# Secondary_Board_1_1.net
KiCad netlist of a schematic drawn in EAGLE
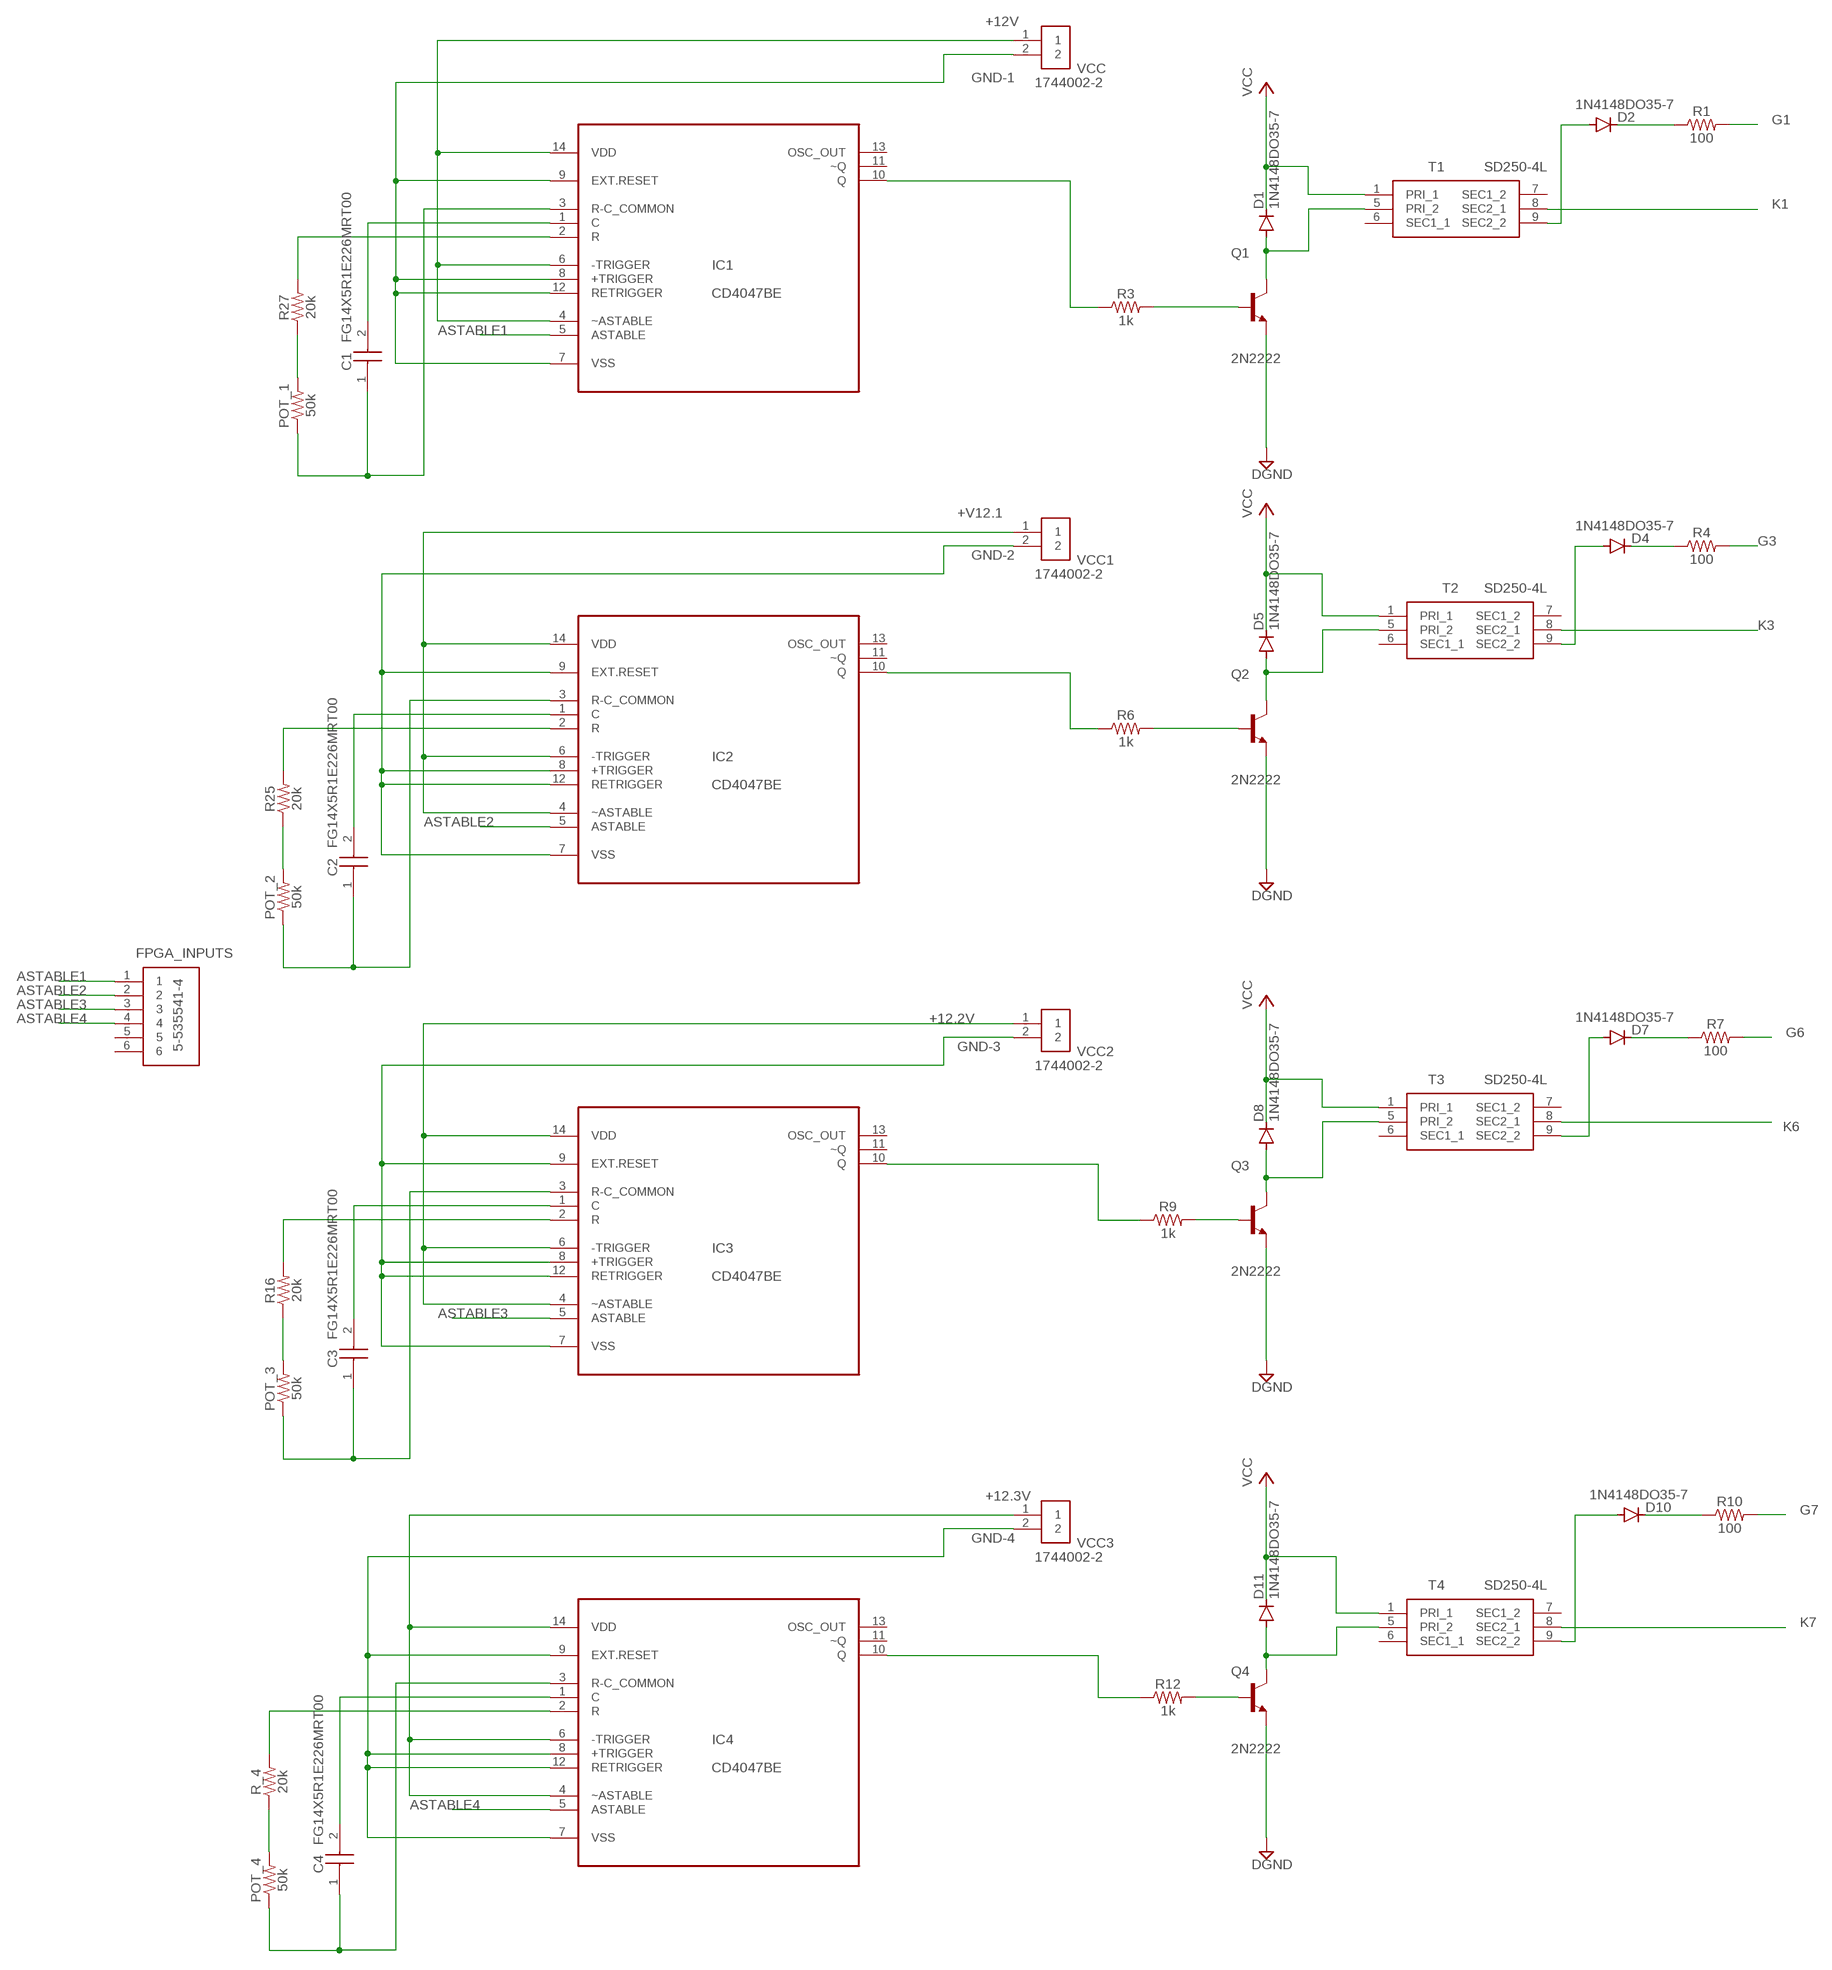
[diagram p0: schematic, sheet 1, part 1 of 2]
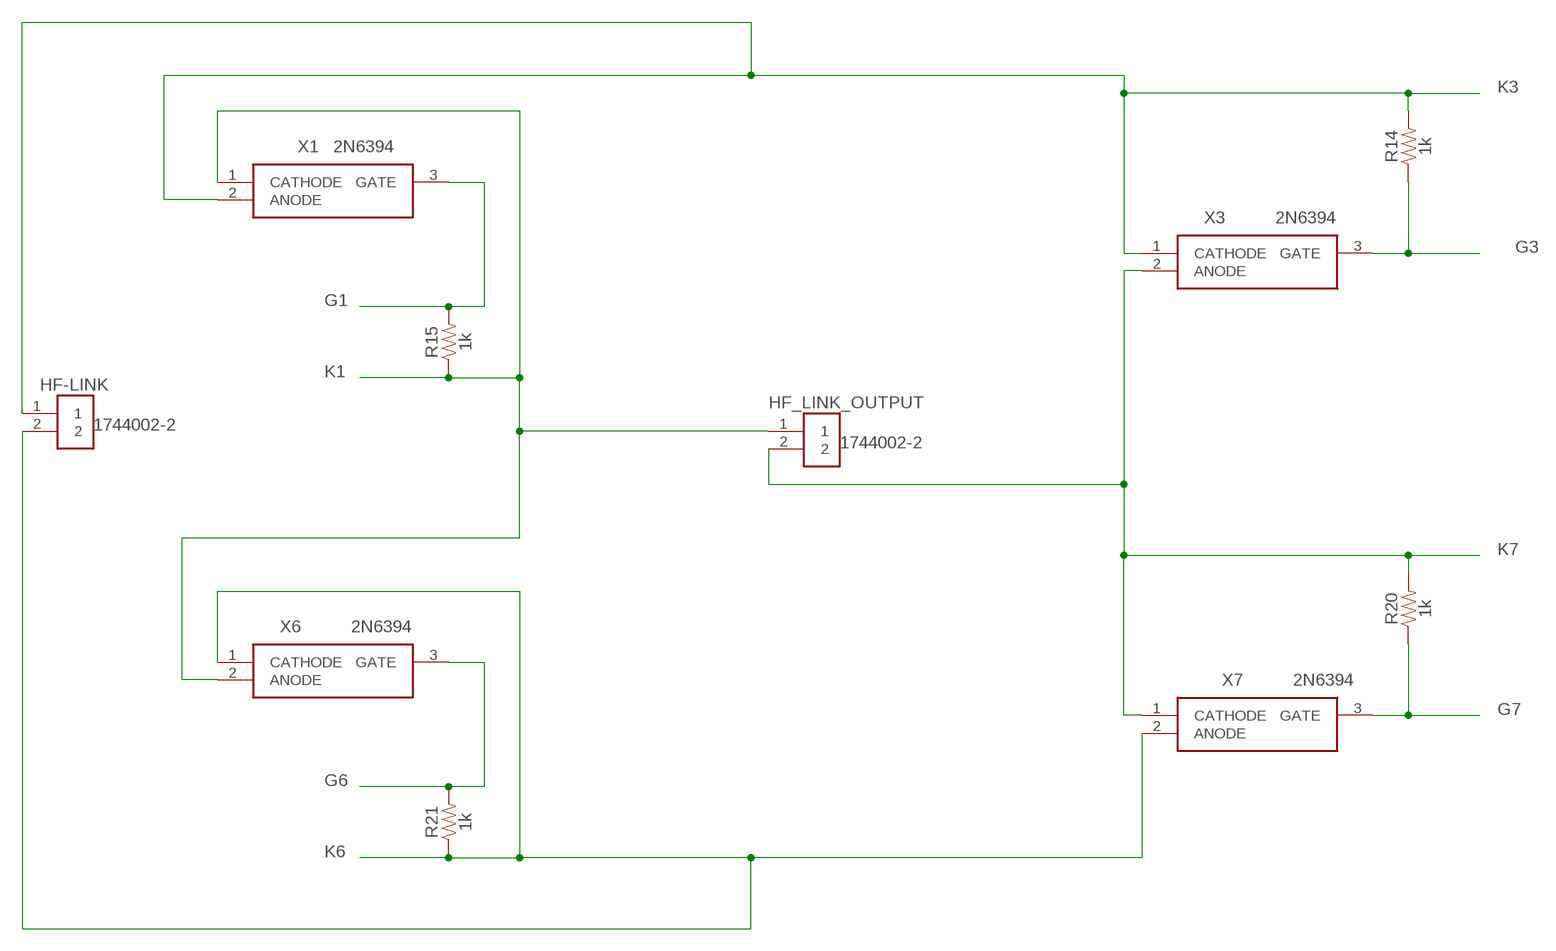
[diagram p1: schematic, sheet 1, part 2 of 2]

(export (version "E")
  (design (tool "Eeschema 10.0.6"))
  (components
    (comp (ref "C1")
      (value "FG14X5R1E226MRT00")
      (footprint "eagle-import:CAPPRD550W50D395H550")
      (libsource (lib "eagle-import") (part "FG14X5R1E226MRT00"))
    )
    (comp (ref "C2")
      (value "FG14X5R1E226MRT00")
      (footprint "eagle-import:CAPPRD550W50D395H550")
      (libsource (lib "eagle-import") (part "FG14X5R1E226MRT00"))
    )
    (comp (ref "C3")
      (value "FG14X5R1E226MRT00")
      (footprint "eagle-import:CAPPRD550W50D395H550")
      (libsource (lib "eagle-import") (part "FG14X5R1E226MRT00"))
    )
    (comp (ref "C4")
      (value "FG14X5R1E226MRT00")
      (footprint "eagle-import:CAPPRD550W50D395H550")
      (libsource (lib "eagle-import") (part "FG14X5R1E226MRT00"))
    )
    (comp (ref "D1")
      (value "1N4148DO35-7")
      (footprint "eagle-import:DO35-7")
      (libsource (lib "eagle-import") (part "1N4148DO35-7"))
    )
    (comp (ref "D2")
      (value "1N4148DO35-7")
      (footprint "eagle-import:DO35-7")
      (libsource (lib "eagle-import") (part "1N4148DO35-7"))
    )
    (comp (ref "D4")
      (value "1N4148DO35-7")
      (footprint "eagle-import:DO35-7")
      (libsource (lib "eagle-import") (part "1N4148DO35-7"))
    )
    (comp (ref "D5")
      (value "1N4148DO35-7")
      (footprint "eagle-import:DO35-7")
      (libsource (lib "eagle-import") (part "1N4148DO35-7"))
    )
    (comp (ref "D7")
      (value "1N4148DO35-7")
      (footprint "eagle-import:DO35-7")
      (libsource (lib "eagle-import") (part "1N4148DO35-7"))
    )
    (comp (ref "D8")
      (value "1N4148DO35-7")
      (footprint "eagle-import:DO35-7")
      (libsource (lib "eagle-import") (part "1N4148DO35-7"))
    )
    (comp (ref "D10")
      (value "1N4148DO35-7")
      (footprint "eagle-import:DO35-7")
      (libsource (lib "eagle-import") (part "1N4148DO35-7"))
    )
    (comp (ref "D11")
      (value "1N4148DO35-7")
      (footprint "eagle-import:DO35-7")
      (libsource (lib "eagle-import") (part "1N4148DO35-7"))
    )
    (comp (ref "FPGA_INPUTS")
      (value "5-535541-4")
      (footprint "eagle-import:SHDR6W76P0X254_1X6_1524X356X62")
      (fields (field (name "MOUSER_PART_NUMBER") "571-5-535541-4"))
      (libsource (lib "eagle-import") (part "5-535541-4"))
    )
    (comp (ref "HF-LINK")
      (value "1744002-2")
      (footprint "eagle-import:CONN_1744002-2")
      (fields (field (name "MF") "TE Connectivity"))
      (libsource (lib "eagle-import") (part "1744002-2"))
    )
    (comp (ref "HF_LINK_OUTPUT")
      (value "1744002-2")
      (footprint "eagle-import:CONN_1744002-2")
      (fields (field (name "MF") "TE Connectivity"))
      (libsource (lib "eagle-import") (part "1744002-2"))
    )
    (comp (ref "IC1")
      (value "CD4047BE")
      (footprint "eagle-import:DIP254P762X508-14")
      (fields (field (name "MF") "Texas Instruments"))
      (libsource (lib "eagle-import") (part "CD4047BE"))
    )
    (comp (ref "IC2")
      (value "CD4047BE")
      (footprint "eagle-import:DIP254P762X508-14")
      (fields (field (name "MF") "Texas Instruments"))
      (libsource (lib "eagle-import") (part "CD4047BE"))
    )
    (comp (ref "IC3")
      (value "CD4047BE")
      (footprint "eagle-import:DIP254P762X508-14")
      (fields (field (name "MF") "Texas Instruments"))
      (libsource (lib "eagle-import") (part "CD4047BE"))
    )
    (comp (ref "IC4")
      (value "CD4047BE")
      (footprint "eagle-import:DIP254P762X508-14")
      (fields (field (name "MF") "Texas Instruments"))
      (libsource (lib "eagle-import") (part "CD4047BE"))
    )
    (comp (ref "POT_1")
      (value "50k")
      (footprint "eagle-import:AXIAL-0.3")
      (libsource (lib "eagle-import") (part "1KOHM-HORIZ-1/4W-1%"))
    )
    (comp (ref "POT_2")
      (value "50k")
      (footprint "eagle-import:AXIAL-0.3")
      (libsource (lib "eagle-import") (part "1KOHM-HORIZ-1/4W-1%"))
    )
    (comp (ref "POT_3")
      (value "50k")
      (footprint "eagle-import:AXIAL-0.3")
      (libsource (lib "eagle-import") (part "1KOHM-HORIZ-1/4W-1%"))
    )
    (comp (ref "POT_4")
      (value "50k")
      (footprint "eagle-import:AXIAL-0.3")
      (libsource (lib "eagle-import") (part "1KOHM-HORIZ-1/4W-1%"))
    )
    (comp (ref "Q1")
      (value "2N2222")
      (footprint "eagle-import:TO127P584H533-3")
      (fields (field (name "MF") "Central Semiconductor"))
      (libsource (lib "eagle-import") (part "2N2222"))
    )
    (comp (ref "Q2")
      (value "2N2222")
      (footprint "eagle-import:TO127P584H533-3")
      (fields (field (name "MF") "Central Semiconductor"))
      (libsource (lib "eagle-import") (part "2N2222"))
    )
    (comp (ref "Q3")
      (value "2N2222")
      (footprint "eagle-import:TO127P584H533-3")
      (fields (field (name "MF") "Central Semiconductor"))
      (libsource (lib "eagle-import") (part "2N2222"))
    )
    (comp (ref "Q4")
      (value "2N2222")
      (footprint "eagle-import:TO127P584H533-3")
      (fields (field (name "MF") "Central Semiconductor"))
      (libsource (lib "eagle-import") (part "2N2222"))
    )
    (comp (ref "R1")
      (value "100")
      (footprint "eagle-import:AXIAL-0.3")
      (libsource (lib "eagle-import") (part "100OHM-HORIZ-1/4W-1%"))
    )
    (comp (ref "R3")
      (value "1k")
      (footprint "eagle-import:AXIAL-0.3")
      (libsource (lib "eagle-import") (part "1KOHM-HORIZ-1/4W-1%"))
    )
    (comp (ref "R4")
      (value "100")
      (footprint "eagle-import:AXIAL-0.3")
      (libsource (lib "eagle-import") (part "100OHM-HORIZ-1/4W-1%"))
    )
    (comp (ref "R6")
      (value "1k")
      (footprint "eagle-import:AXIAL-0.3")
      (libsource (lib "eagle-import") (part "1KOHM-HORIZ-1/4W-1%"))
    )
    (comp (ref "R7")
      (value "100")
      (footprint "eagle-import:AXIAL-0.3")
      (libsource (lib "eagle-import") (part "100OHM-HORIZ-1/4W-1%"))
    )
    (comp (ref "R9")
      (value "1k")
      (footprint "eagle-import:AXIAL-0.3")
      (libsource (lib "eagle-import") (part "1KOHM-HORIZ-1/4W-1%"))
    )
    (comp (ref "R10")
      (value "100")
      (footprint "eagle-import:AXIAL-0.3")
      (libsource (lib "eagle-import") (part "100OHM-HORIZ-1/4W-1%"))
    )
    (comp (ref "R12")
      (value "1k")
      (footprint "eagle-import:AXIAL-0.3")
      (libsource (lib "eagle-import") (part "1KOHM-HORIZ-1/4W-1%"))
    )
    (comp (ref "R14")
      (value "1k")
      (footprint "eagle-import:AXIAL-0.3")
      (libsource (lib "eagle-import") (part "1KOHM-HORIZ-1/4W-1%"))
    )
    (comp (ref "R15")
      (value "1k")
      (footprint "eagle-import:AXIAL-0.3")
      (libsource (lib "eagle-import") (part "1KOHM-HORIZ-1/4W-1%"))
    )
    (comp (ref "R16")
      (value "20k")
      (footprint "eagle-import:AXIAL-0.3")
      (libsource (lib "eagle-import") (part "1KOHM-HORIZ-1/4W-1%"))
    )
    (comp (ref "R20")
      (value "1k")
      (footprint "eagle-import:AXIAL-0.3")
      (libsource (lib "eagle-import") (part "1KOHM-HORIZ-1/4W-1%"))
    )
    (comp (ref "R21")
      (value "1k")
      (footprint "eagle-import:AXIAL-0.3")
      (libsource (lib "eagle-import") (part "1KOHM-HORIZ-1/4W-1%"))
    )
    (comp (ref "R25")
      (value "20k")
      (footprint "eagle-import:AXIAL-0.3")
      (libsource (lib "eagle-import") (part "1KOHM-HORIZ-1/4W-1%"))
    )
    (comp (ref "R27")
      (value "20k")
      (footprint "eagle-import:AXIAL-0.3")
      (libsource (lib "eagle-import") (part "1KOHM-HORIZ-1/4W-1%"))
    )
    (comp (ref "R_4")
      (value "20k")
      (footprint "eagle-import:AXIAL-0.3")
      (libsource (lib "eagle-import") (part "1KOHM-HORIZ-1/4W-1%"))
    )
    (comp (ref "T1")
      (value "SD250-4L")
      (footprint "eagle-import:SD2504L")
      (libsource (lib "eagle-import") (part "SD250-4L"))
    )
    (comp (ref "T2")
      (value "SD250-4L")
      (footprint "eagle-import:SD2504L")
      (libsource (lib "eagle-import") (part "SD250-4L"))
    )
    (comp (ref "T3")
      (value "SD250-4L")
      (footprint "eagle-import:SD2504L")
      (libsource (lib "eagle-import") (part "SD250-4L"))
    )
    (comp (ref "T4")
      (value "SD250-4L")
      (footprint "eagle-import:SD2504L")
      (libsource (lib "eagle-import") (part "SD250-4L"))
    )
    (comp (ref "VCC")
      (value "1744002-2")
      (footprint "eagle-import:CONN_1744002-2")
      (fields (field (name "MF") "TE Connectivity"))
      (libsource (lib "eagle-import") (part "1744002-2"))
    )
    (comp (ref "VCC1")
      (value "1744002-2")
      (footprint "eagle-import:CONN_1744002-2")
      (fields (field (name "MF") "TE Connectivity"))
      (libsource (lib "eagle-import") (part "1744002-2"))
    )
    (comp (ref "VCC2")
      (value "1744002-2")
      (footprint "eagle-import:CONN_1744002-2")
      (fields (field (name "MF") "TE Connectivity"))
      (libsource (lib "eagle-import") (part "1744002-2"))
    )
    (comp (ref "VCC3")
      (value "1744002-2")
      (footprint "eagle-import:CONN_1744002-2")
      (fields (field (name "MF") "TE Connectivity"))
      (libsource (lib "eagle-import") (part "1744002-2"))
    )
    (comp (ref "X1")
      (value "2N6394")
      (footprint "eagle-import:TO254P482X997X2018-3P")
      (fields (field (name "MOUSER_PART_NUMBER") "863-2N6394"))
      (libsource (lib "eagle-import") (part "2N6394"))
    )
    (comp (ref "X3")
      (value "2N6394")
      (footprint "eagle-import:TO254P482X997X2018-3P")
      (fields (field (name "MOUSER_PART_NUMBER") "863-2N6394"))
      (libsource (lib "eagle-import") (part "2N6394"))
    )
    (comp (ref "X6")
      (value "2N6394")
      (footprint "eagle-import:TO254P482X997X2018-3P")
      (fields (field (name "MOUSER_PART_NUMBER") "863-2N6394"))
      (libsource (lib "eagle-import") (part "2N6394"))
    )
    (comp (ref "X7")
      (value "2N6394")
      (footprint "eagle-import:TO254P482X997X2018-3P")
      (fields (field (name "MOUSER_PART_NUMBER") "863-2N6394"))
      (libsource (lib "eagle-import") (part "2N6394"))
    )
  )
  (nets
    (net (code "1") (name "/+12.2V") (class "Default")
      (node (ref "IC3") (pin "14") (pinfunction "VDD_14") (pintype "power_in"))
      (node (ref "IC3") (pin "4") (pinfunction "~{ASTABLE}_4") (pintype "input"))
      (node (ref "IC3") (pin "6") (pinfunction "-TRIGGER_6") (pintype "power_in"))
      (node (ref "VCC2") (pin "1") (pinfunction "1_1") (pintype "passive"))
    )
    (net (code "2") (name "/+12.3V") (class "Default")
      (node (ref "IC4") (pin "14") (pinfunction "VDD_14") (pintype "power_in"))
      (node (ref "IC4") (pin "4") (pinfunction "~{ASTABLE}_4") (pintype "input"))
      (node (ref "IC4") (pin "6") (pinfunction "-TRIGGER_6") (pintype "power_in"))
      (node (ref "VCC3") (pin "1") (pinfunction "1_1") (pintype "passive"))
    )
    (net (code "3") (name "/+12V") (class "Default")
      (node (ref "IC1") (pin "14") (pinfunction "VDD_14") (pintype "power_in"))
      (node (ref "IC1") (pin "4") (pinfunction "~{ASTABLE}_4") (pintype "input"))
      (node (ref "IC1") (pin "6") (pinfunction "-TRIGGER_6") (pintype "power_in"))
      (node (ref "VCC") (pin "1") (pinfunction "1_1") (pintype "passive"))
    )
    (net (code "4") (name "/+V12.1") (class "Default")
      (node (ref "IC2") (pin "14") (pinfunction "VDD_14") (pintype "power_in"))
      (node (ref "IC2") (pin "4") (pinfunction "~{ASTABLE}_4") (pintype "input"))
      (node (ref "IC2") (pin "6") (pinfunction "-TRIGGER_6") (pintype "power_in"))
      (node (ref "VCC1") (pin "1") (pinfunction "1_1") (pintype "passive"))
    )
    (net (code "5") (name "/ASTABLE1") (class "Default")
      (node (ref "FPGA_INPUTS") (pin "1") (pinfunction "1_1") (pintype "bidirectional"))
      (node (ref "IC1") (pin "5") (pinfunction "ASTABLE_5") (pintype "input"))
    )
    (net (code "6") (name "/ASTABLE2") (class "Default")
      (node (ref "FPGA_INPUTS") (pin "2") (pinfunction "2_2") (pintype "bidirectional"))
      (node (ref "IC2") (pin "5") (pinfunction "ASTABLE_5") (pintype "input"))
    )
    (net (code "7") (name "/ASTABLE3") (class "Default")
      (node (ref "FPGA_INPUTS") (pin "3") (pinfunction "3_3") (pintype "bidirectional"))
      (node (ref "IC3") (pin "5") (pinfunction "ASTABLE_5") (pintype "input"))
    )
    (net (code "8") (name "/ASTABLE4") (class "Default")
      (node (ref "FPGA_INPUTS") (pin "4") (pinfunction "4_4") (pintype "bidirectional"))
      (node (ref "IC4") (pin "5") (pinfunction "ASTABLE_5") (pintype "input"))
    )
    (net (code "9") (name "/G1") (class "Default")
      (node (ref "R1") (pin "P$2") (pinfunction "2_P$2") (pintype "passive"))
      (node (ref "R15") (pin "P$2") (pinfunction "2_P$2") (pintype "passive"))
      (node (ref "X1") (pin "3") (pinfunction "GATE_3") (pintype "bidirectional"))
    )
    (net (code "10") (name "/G3") (class "Default")
      (node (ref "R14") (pin "P$1") (pinfunction "1_P$1") (pintype "passive"))
      (node (ref "R4") (pin "P$2") (pinfunction "2_P$2") (pintype "passive"))
      (node (ref "X3") (pin "3") (pinfunction "GATE_3") (pintype "bidirectional"))
    )
    (net (code "11") (name "/G6") (class "Default")
      (node (ref "R21") (pin "P$2") (pinfunction "2_P$2") (pintype "passive"))
      (node (ref "R7") (pin "P$2") (pinfunction "2_P$2") (pintype "passive"))
      (node (ref "X6") (pin "3") (pinfunction "GATE_3") (pintype "bidirectional"))
    )
    (net (code "12") (name "/G7") (class "Default")
      (node (ref "R10") (pin "P$2") (pinfunction "2_P$2") (pintype "passive"))
      (node (ref "R20") (pin "P$1") (pinfunction "1_P$1") (pintype "passive"))
      (node (ref "X7") (pin "3") (pinfunction "GATE_3") (pintype "bidirectional"))
    )
    (net (code "13") (name "/GND-1") (class "Default")
      (node (ref "IC1") (pin "12") (pinfunction "RETRIGGER_12") (pintype "input"))
      (node (ref "IC1") (pin "7") (pinfunction "VSS_7") (pintype "power_in"))
      (node (ref "IC1") (pin "8") (pinfunction "+TRIGGER_8") (pintype "input"))
      (node (ref "IC1") (pin "9") (pinfunction "EXT.RESET_9") (pintype "input"))
      (node (ref "VCC") (pin "2") (pinfunction "2_2") (pintype "passive"))
    )
    (net (code "14") (name "/GND-2") (class "Default")
      (node (ref "IC2") (pin "12") (pinfunction "RETRIGGER_12") (pintype "input"))
      (node (ref "IC2") (pin "7") (pinfunction "VSS_7") (pintype "power_in"))
      (node (ref "IC2") (pin "8") (pinfunction "+TRIGGER_8") (pintype "input"))
      (node (ref "IC2") (pin "9") (pinfunction "EXT.RESET_9") (pintype "input"))
      (node (ref "VCC1") (pin "2") (pinfunction "2_2") (pintype "passive"))
    )
    (net (code "15") (name "/GND-3") (class "Default")
      (node (ref "IC3") (pin "12") (pinfunction "RETRIGGER_12") (pintype "input"))
      (node (ref "IC3") (pin "7") (pinfunction "VSS_7") (pintype "power_in"))
      (node (ref "IC3") (pin "8") (pinfunction "+TRIGGER_8") (pintype "input"))
      (node (ref "IC3") (pin "9") (pinfunction "EXT.RESET_9") (pintype "input"))
      (node (ref "VCC2") (pin "2") (pinfunction "2_2") (pintype "passive"))
    )
    (net (code "16") (name "/GND-4") (class "Default")
      (node (ref "IC4") (pin "12") (pinfunction "RETRIGGER_12") (pintype "input"))
      (node (ref "IC4") (pin "7") (pinfunction "VSS_7") (pintype "power_in"))
      (node (ref "IC4") (pin "8") (pinfunction "+TRIGGER_8") (pintype "input"))
      (node (ref "IC4") (pin "9") (pinfunction "EXT.RESET_9") (pintype "input"))
      (node (ref "VCC3") (pin "2") (pinfunction "2_2") (pintype "passive"))
    )
    (net (code "17") (name "/K1") (class "Default")
      (node (ref "HF_LINK_OUTPUT") (pin "1") (pinfunction "1_1") (pintype "passive"))
      (node (ref "R15") (pin "P$1") (pinfunction "1_P$1") (pintype "passive"))
      (node (ref "T1") (pin "8") (pinfunction "SEC2_1_8") (pintype "bidirectional"))
      (node (ref "X1") (pin "1") (pinfunction "CATHODE_1") (pintype "bidirectional"))
      (node (ref "X6") (pin "2") (pinfunction "ANODE_2") (pintype "bidirectional"))
    )
    (net (code "18") (name "/K3") (class "Default")
      (node (ref "HF-LINK") (pin "1") (pinfunction "1_1") (pintype "passive"))
      (node (ref "R14") (pin "P$2") (pinfunction "2_P$2") (pintype "passive"))
      (node (ref "T2") (pin "8") (pinfunction "SEC2_1_8") (pintype "bidirectional"))
      (node (ref "X1") (pin "2") (pinfunction "ANODE_2") (pintype "bidirectional"))
      (node (ref "X3") (pin "1") (pinfunction "CATHODE_1") (pintype "bidirectional"))
    )
    (net (code "19") (name "/K6") (class "Default")
      (node (ref "HF-LINK") (pin "2") (pinfunction "2_2") (pintype "passive"))
      (node (ref "R21") (pin "P$1") (pinfunction "1_P$1") (pintype "passive"))
      (node (ref "T3") (pin "8") (pinfunction "SEC2_1_8") (pintype "bidirectional"))
      (node (ref "X6") (pin "1") (pinfunction "CATHODE_1") (pintype "bidirectional"))
      (node (ref "X7") (pin "2") (pinfunction "ANODE_2") (pintype "bidirectional"))
    )
    (net (code "20") (name "/K7") (class "Default")
      (node (ref "HF_LINK_OUTPUT") (pin "2") (pinfunction "2_2") (pintype "passive"))
      (node (ref "R20") (pin "P$2") (pinfunction "2_P$2") (pintype "passive"))
      (node (ref "T4") (pin "8") (pinfunction "SEC2_1_8") (pintype "bidirectional"))
      (node (ref "X3") (pin "2") (pinfunction "ANODE_2") (pintype "bidirectional"))
      (node (ref "X7") (pin "1") (pinfunction "CATHODE_1") (pintype "bidirectional"))
    )
    (net (code "21") (name "DGND") (class "Default")
      (node (ref "Q1") (pin "1") (pinfunction "E_1") (pintype "passive"))
      (node (ref "Q2") (pin "1") (pinfunction "E_1") (pintype "passive"))
      (node (ref "Q3") (pin "1") (pinfunction "E_1") (pintype "passive"))
      (node (ref "Q4") (pin "1") (pinfunction "E_1") (pintype "passive"))
    )
    (net (code "22") (name "Net-(C1-+)") (class "Default")
      (node (ref "C1") (pin "1") (pinfunction "+_1") (pintype "bidirectional"))
      (node (ref "IC1") (pin "3") (pinfunction "R-C_COMMON_3") (pintype "input"))
      (node (ref "POT_1") (pin "P$1") (pinfunction "1_P$1") (pintype "passive"))
    )
    (net (code "23") (name "Net-(C1--)") (class "Default")
      (node (ref "C1") (pin "2") (pinfunction "-_2") (pintype "bidirectional"))
      (node (ref "IC1") (pin "1") (pinfunction "C_1") (pintype "input"))
    )
    (net (code "24") (name "Net-(C2-+)") (class "Default")
      (node (ref "C2") (pin "1") (pinfunction "+_1") (pintype "bidirectional"))
      (node (ref "IC2") (pin "3") (pinfunction "R-C_COMMON_3") (pintype "input"))
      (node (ref "POT_2") (pin "P$1") (pinfunction "1_P$1") (pintype "passive"))
    )
    (net (code "25") (name "Net-(C2--)") (class "Default")
      (node (ref "C2") (pin "2") (pinfunction "-_2") (pintype "bidirectional"))
      (node (ref "IC2") (pin "1") (pinfunction "C_1") (pintype "input"))
    )
    (net (code "26") (name "Net-(C3-+)") (class "Default")
      (node (ref "C3") (pin "1") (pinfunction "+_1") (pintype "bidirectional"))
      (node (ref "IC3") (pin "3") (pinfunction "R-C_COMMON_3") (pintype "input"))
      (node (ref "POT_3") (pin "P$1") (pinfunction "1_P$1") (pintype "passive"))
    )
    (net (code "27") (name "Net-(C3--)") (class "Default")
      (node (ref "C3") (pin "2") (pinfunction "-_2") (pintype "bidirectional"))
      (node (ref "IC3") (pin "1") (pinfunction "C_1") (pintype "input"))
    )
    (net (code "28") (name "Net-(C4-+)") (class "Default")
      (node (ref "C4") (pin "1") (pinfunction "+_1") (pintype "bidirectional"))
      (node (ref "IC4") (pin "3") (pinfunction "R-C_COMMON_3") (pintype "input"))
      (node (ref "POT_4") (pin "P$1") (pinfunction "1_P$1") (pintype "passive"))
    )
    (net (code "29") (name "Net-(C4--)") (class "Default")
      (node (ref "C4") (pin "2") (pinfunction "-_2") (pintype "bidirectional"))
      (node (ref "IC4") (pin "1") (pinfunction "C_1") (pintype "input"))
    )
    (net (code "30") (name "Net-(IC1-Q)") (class "Default")
      (node (ref "IC1") (pin "10") (pinfunction "Q_10") (pintype "output"))
      (node (ref "R3") (pin "P$1") (pinfunction "1_P$1") (pintype "passive"))
    )
    (net (code "31") (name "Net-(IC1-R)") (class "Default")
      (node (ref "IC1") (pin "2") (pinfunction "R_2") (pintype "input"))
      (node (ref "R27") (pin "P$2") (pinfunction "2_P$2") (pintype "passive"))
    )
    (net (code "32") (name "Net-(IC2-Q)") (class "Default")
      (node (ref "IC2") (pin "10") (pinfunction "Q_10") (pintype "output"))
      (node (ref "R6") (pin "P$1") (pinfunction "1_P$1") (pintype "passive"))
    )
    (net (code "33") (name "Net-(IC2-R)") (class "Default")
      (node (ref "IC2") (pin "2") (pinfunction "R_2") (pintype "input"))
      (node (ref "R25") (pin "P$2") (pinfunction "2_P$2") (pintype "passive"))
    )
    (net (code "34") (name "Net-(IC3-Q)") (class "Default")
      (node (ref "IC3") (pin "10") (pinfunction "Q_10") (pintype "output"))
      (node (ref "R9") (pin "P$1") (pinfunction "1_P$1") (pintype "passive"))
    )
    (net (code "35") (name "Net-(IC3-R)") (class "Default")
      (node (ref "IC3") (pin "2") (pinfunction "R_2") (pintype "input"))
      (node (ref "R16") (pin "P$2") (pinfunction "2_P$2") (pintype "passive"))
    )
    (net (code "36") (name "Net-(IC4-Q)") (class "Default")
      (node (ref "IC4") (pin "10") (pinfunction "Q_10") (pintype "output"))
      (node (ref "R12") (pin "P$1") (pinfunction "1_P$1") (pintype "passive"))
    )
    (net (code "37") (name "Net-(IC4-R)") (class "Default")
      (node (ref "IC4") (pin "2") (pinfunction "R_2") (pintype "input"))
      (node (ref "R_4") (pin "P$2") (pinfunction "2_P$2") (pintype "passive"))
    )
    (net (code "38") (name "Net-(POT_1-2)") (class "Default")
      (node (ref "POT_1") (pin "P$2") (pinfunction "2_P$2") (pintype "passive"))
      (node (ref "R27") (pin "P$1") (pinfunction "1_P$1") (pintype "passive"))
    )
    (net (code "39") (name "Net-(POT_2-2)") (class "Default")
      (node (ref "POT_2") (pin "P$2") (pinfunction "2_P$2") (pintype "passive"))
      (node (ref "R25") (pin "P$1") (pinfunction "1_P$1") (pintype "passive"))
    )
    (net (code "40") (name "Net-(POT_3-2)") (class "Default")
      (node (ref "POT_3") (pin "P$2") (pinfunction "2_P$2") (pintype "passive"))
      (node (ref "R16") (pin "P$1") (pinfunction "1_P$1") (pintype "passive"))
    )
    (net (code "41") (name "Net-(POT_4-2)") (class "Default")
      (node (ref "POT_4") (pin "P$2") (pinfunction "2_P$2") (pintype "passive"))
      (node (ref "R_4") (pin "P$1") (pinfunction "1_P$1") (pintype "passive"))
    )
    (net (code "42") (name "Net-(Q1-B)") (class "Default")
      (node (ref "Q1") (pin "2") (pinfunction "B_2") (pintype "passive"))
      (node (ref "R3") (pin "P$2") (pinfunction "2_P$2") (pintype "passive"))
    )
    (net (code "43") (name "Net-(Q1-C)") (class "Default")
      (node (ref "D1") (pin "A") (pinfunction "A_A") (pintype "passive"))
      (node (ref "Q1") (pin "3") (pinfunction "C_3") (pintype "passive"))
      (node (ref "T1") (pin "5") (pinfunction "PRI_2_5") (pintype "bidirectional"))
    )
    (net (code "44") (name "Net-(Q2-B)") (class "Default")
      (node (ref "Q2") (pin "2") (pinfunction "B_2") (pintype "passive"))
      (node (ref "R6") (pin "P$2") (pinfunction "2_P$2") (pintype "passive"))
    )
    (net (code "45") (name "Net-(Q2-C)") (class "Default")
      (node (ref "D5") (pin "A") (pinfunction "A_A") (pintype "passive"))
      (node (ref "Q2") (pin "3") (pinfunction "C_3") (pintype "passive"))
      (node (ref "T2") (pin "5") (pinfunction "PRI_2_5") (pintype "bidirectional"))
    )
    (net (code "46") (name "Net-(Q3-B)") (class "Default")
      (node (ref "Q3") (pin "2") (pinfunction "B_2") (pintype "passive"))
      (node (ref "R9") (pin "P$2") (pinfunction "2_P$2") (pintype "passive"))
    )
    (net (code "47") (name "Net-(Q3-C)") (class "Default")
      (node (ref "D8") (pin "A") (pinfunction "A_A") (pintype "passive"))
      (node (ref "Q3") (pin "3") (pinfunction "C_3") (pintype "passive"))
      (node (ref "T3") (pin "5") (pinfunction "PRI_2_5") (pintype "bidirectional"))
    )
    (net (code "48") (name "Net-(Q4-B)") (class "Default")
      (node (ref "Q4") (pin "2") (pinfunction "B_2") (pintype "passive"))
      (node (ref "R12") (pin "P$2") (pinfunction "2_P$2") (pintype "passive"))
    )
    (net (code "49") (name "Net-(Q4-C)") (class "Default")
      (node (ref "D11") (pin "A") (pinfunction "A_A") (pintype "passive"))
      (node (ref "Q4") (pin "3") (pinfunction "C_3") (pintype "passive"))
      (node (ref "T4") (pin "5") (pinfunction "PRI_2_5") (pintype "bidirectional"))
    )
    (net (code "50") (name "Net-(R1-1)") (class "Default")
      (node (ref "D2") (pin "C") (pinfunction "C_C") (pintype "passive"))
      (node (ref "R1") (pin "P$1") (pinfunction "1_P$1") (pintype "passive"))
    )
    (net (code "51") (name "Net-(R4-1)") (class "Default")
      (node (ref "D4") (pin "C") (pinfunction "C_C") (pintype "passive"))
      (node (ref "R4") (pin "P$1") (pinfunction "1_P$1") (pintype "passive"))
    )
    (net (code "52") (name "Net-(R7-1)") (class "Default")
      (node (ref "D7") (pin "C") (pinfunction "C_C") (pintype "passive"))
      (node (ref "R7") (pin "P$1") (pinfunction "1_P$1") (pintype "passive"))
    )
    (net (code "53") (name "Net-(R10-1)") (class "Default")
      (node (ref "D10") (pin "C") (pinfunction "C_C") (pintype "passive"))
      (node (ref "R10") (pin "P$1") (pinfunction "1_P$1") (pintype "passive"))
    )
    (net (code "54") (name "Net-(T1-SEC2_2)") (class "Default")
      (node (ref "D2") (pin "A") (pinfunction "A_A") (pintype "passive"))
      (node (ref "T1") (pin "9") (pinfunction "SEC2_2_9") (pintype "bidirectional"))
    )
    (net (code "55") (name "Net-(T2-SEC2_2)") (class "Default")
      (node (ref "D4") (pin "A") (pinfunction "A_A") (pintype "passive"))
      (node (ref "T2") (pin "9") (pinfunction "SEC2_2_9") (pintype "bidirectional"))
    )
    (net (code "56") (name "Net-(T3-SEC2_2)") (class "Default")
      (node (ref "D7") (pin "A") (pinfunction "A_A") (pintype "passive"))
      (node (ref "T3") (pin "9") (pinfunction "SEC2_2_9") (pintype "bidirectional"))
    )
    (net (code "57") (name "Net-(T4-SEC2_2)") (class "Default")
      (node (ref "D10") (pin "A") (pinfunction "A_A") (pintype "passive"))
      (node (ref "T4") (pin "9") (pinfunction "SEC2_2_9") (pintype "bidirectional"))
    )
    (net (code "58") (name "VCC") (class "Default")
      (node (ref "D1") (pin "C") (pinfunction "C_C") (pintype "passive"))
      (node (ref "D11") (pin "C") (pinfunction "C_C") (pintype "passive"))
      (node (ref "D5") (pin "C") (pinfunction "C_C") (pintype "passive"))
      (node (ref "D8") (pin "C") (pinfunction "C_C") (pintype "passive"))
      (node (ref "T1") (pin "1") (pinfunction "PRI_1_1") (pintype "bidirectional"))
      (node (ref "T2") (pin "1") (pinfunction "PRI_1_1") (pintype "bidirectional"))
      (node (ref "T3") (pin "1") (pinfunction "PRI_1_1") (pintype "bidirectional"))
      (node (ref "T4") (pin "1") (pinfunction "PRI_1_1") (pintype "bidirectional"))
    )
    (net (code "59") (name "unconnected-(FPGA_INPUTS-Pad5)") (class "Default")
      (node (ref "FPGA_INPUTS") (pin "5") (pinfunction "5_5") (pintype "bidirectional"))
    )
    (net (code "60") (name "unconnected-(FPGA_INPUTS-Pad6)") (class "Default")
      (node (ref "FPGA_INPUTS") (pin "6") (pinfunction "6_6") (pintype "bidirectional"))
    )
    (net (code "61") (name "unconnected-(IC1-OSC_OUT-Pad13)") (class "Default")
      (node (ref "IC1") (pin "13") (pinfunction "OSC_OUT_13") (pintype "output"))
    )
    (net (code "62") (name "unconnected-(IC1-~{Q}-Pad11)") (class "Default")
      (node (ref "IC1") (pin "11") (pinfunction "~{Q}_11") (pintype "output"))
    )
    (net (code "63") (name "unconnected-(IC2-OSC_OUT-Pad13)") (class "Default")
      (node (ref "IC2") (pin "13") (pinfunction "OSC_OUT_13") (pintype "output"))
    )
    (net (code "64") (name "unconnected-(IC2-~{Q}-Pad11)") (class "Default")
      (node (ref "IC2") (pin "11") (pinfunction "~{Q}_11") (pintype "output"))
    )
    (net (code "65") (name "unconnected-(IC3-OSC_OUT-Pad13)") (class "Default")
      (node (ref "IC3") (pin "13") (pinfunction "OSC_OUT_13") (pintype "output"))
    )
    (net (code "66") (name "unconnected-(IC3-~{Q}-Pad11)") (class "Default")
      (node (ref "IC3") (pin "11") (pinfunction "~{Q}_11") (pintype "output"))
    )
    (net (code "67") (name "unconnected-(IC4-OSC_OUT-Pad13)") (class "Default")
      (node (ref "IC4") (pin "13") (pinfunction "OSC_OUT_13") (pintype "output"))
    )
    (net (code "68") (name "unconnected-(IC4-~{Q}-Pad11)") (class "Default")
      (node (ref "IC4") (pin "11") (pinfunction "~{Q}_11") (pintype "output"))
    )
    (net (code "69") (name "unconnected-(T1-SEC1_1-Pad6)") (class "Default")
      (node (ref "T1") (pin "6") (pinfunction "SEC1_1_6") (pintype "bidirectional"))
    )
    (net (code "70") (name "unconnected-(T1-SEC1_2-Pad7)") (class "Default")
      (node (ref "T1") (pin "7") (pinfunction "SEC1_2_7") (pintype "bidirectional"))
    )
    (net (code "71") (name "unconnected-(T2-SEC1_1-Pad6)") (class "Default")
      (node (ref "T2") (pin "6") (pinfunction "SEC1_1_6") (pintype "bidirectional"))
    )
    (net (code "72") (name "unconnected-(T2-SEC1_2-Pad7)") (class "Default")
      (node (ref "T2") (pin "7") (pinfunction "SEC1_2_7") (pintype "bidirectional"))
    )
    (net (code "73") (name "unconnected-(T3-SEC1_1-Pad6)") (class "Default")
      (node (ref "T3") (pin "6") (pinfunction "SEC1_1_6") (pintype "bidirectional"))
    )
    (net (code "74") (name "unconnected-(T3-SEC1_2-Pad7)") (class "Default")
      (node (ref "T3") (pin "7") (pinfunction "SEC1_2_7") (pintype "bidirectional"))
    )
    (net (code "75") (name "unconnected-(T4-SEC1_1-Pad6)") (class "Default")
      (node (ref "T4") (pin "6") (pinfunction "SEC1_1_6") (pintype "bidirectional"))
    )
    (net (code "76") (name "unconnected-(T4-SEC1_2-Pad7)") (class "Default")
      (node (ref "T4") (pin "7") (pinfunction "SEC1_2_7") (pintype "bidirectional"))
    )
  )
)
